# FiveLEDs.net
KiCad netlist of a schematic drawn in EAGLE
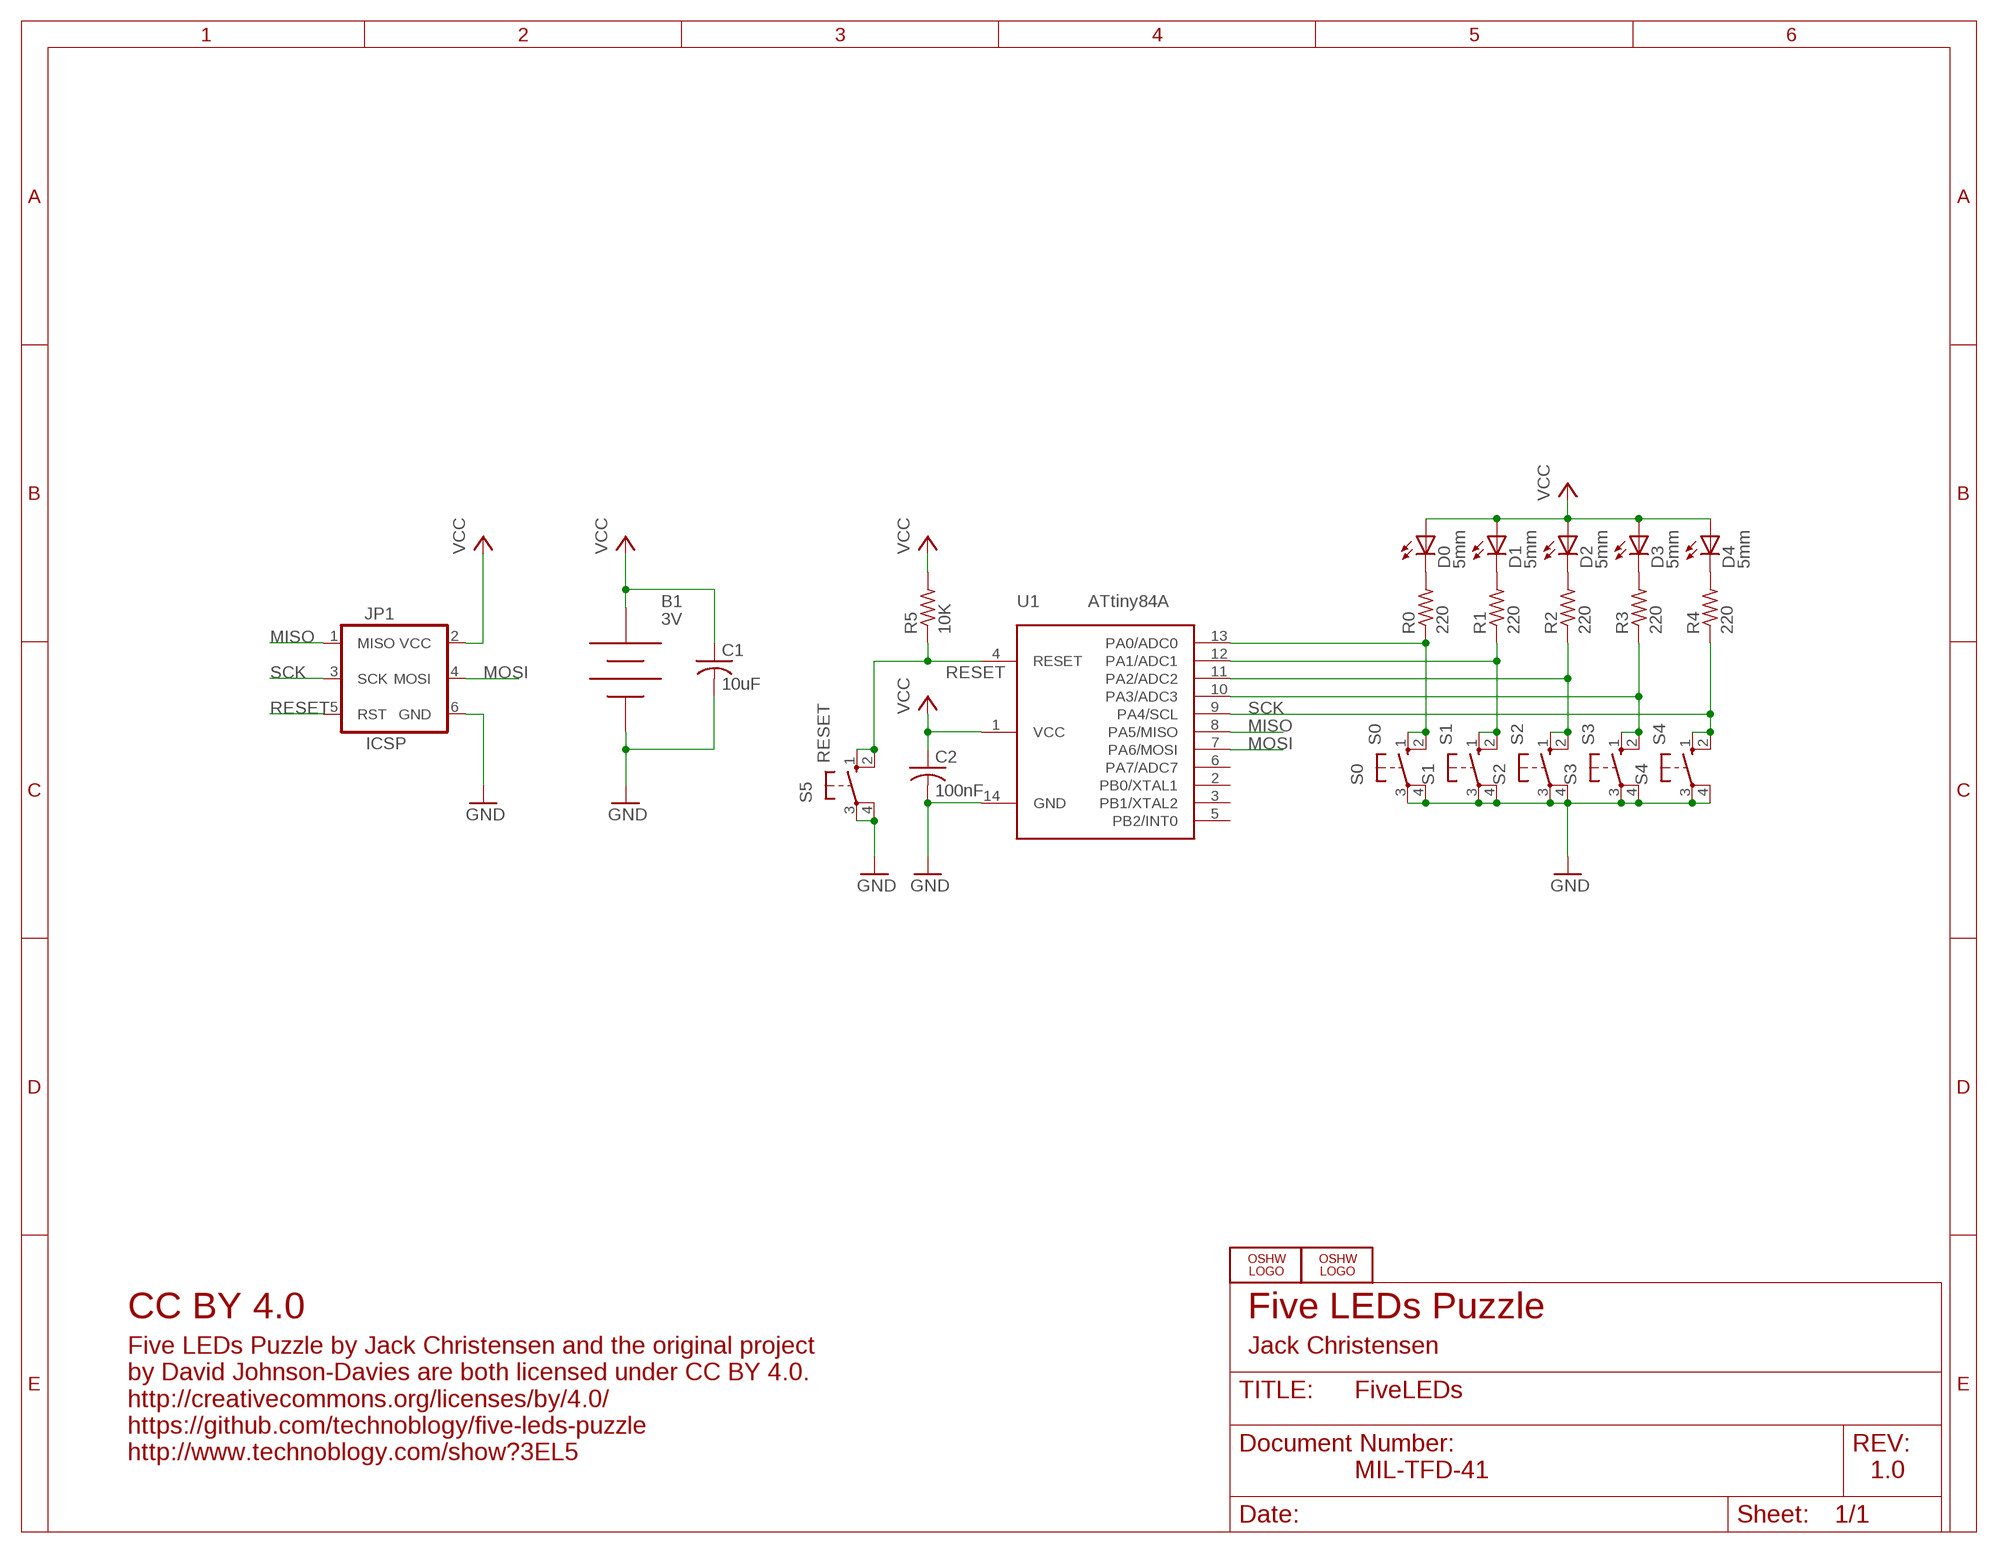
[diagram p0: schematic, sheet 1]

(export (version "E")
  (design (tool "Eeschema 10.0.6"))
  (components
    (comp (ref "B1")
      (value "3V")
      (footprint "eagle-import:KEYSTONE-2462-NO-HOLES")
      (libsource (lib "eagle-import") (part "BATTERY-2AANOHOLES"))
    )
    (comp (ref "C1")
      (value "10uF")
      (footprint "eagle-import:M0805")
      (libsource (lib "eagle-import") (part "C-USM0805"))
    )
    (comp (ref "C2")
      (value "100nF")
      (footprint "eagle-import:M0805")
      (libsource (lib "eagle-import") (part "C-USM0805"))
    )
    (comp (ref "D0")
      (value "5mm")
      (footprint "eagle-import:LED5MM")
      (libsource (lib "eagle-import") (part "LED5MM"))
    )
    (comp (ref "D1")
      (value "5mm")
      (footprint "eagle-import:LED5MM")
      (libsource (lib "eagle-import") (part "LED5MM"))
    )
    (comp (ref "D2")
      (value "5mm")
      (footprint "eagle-import:LED5MM")
      (libsource (lib "eagle-import") (part "LED5MM"))
    )
    (comp (ref "D3")
      (value "5mm")
      (footprint "eagle-import:LED5MM")
      (libsource (lib "eagle-import") (part "LED5MM"))
    )
    (comp (ref "D4")
      (value "5mm")
      (footprint "eagle-import:LED5MM")
      (libsource (lib "eagle-import") (part "LED5MM"))
    )
    (comp (ref "JP1")
      (value "ICSP")
      (footprint "eagle-import:2X3_LOCK")
      (libsource (lib "eagle-import") (part "AVR_SPI_PRG_62X3_LOCK"))
    )
    (comp (ref "LOGO1")
      (value "OSHW_LOGO_8MILX0150-NT")
      (footprint "eagle-import:OSHW_8X150_NOTEXT")
      (libsource (lib "eagle-import") (part "OSHW_LOGO_8MILX0150-NT"))
    )
    (comp (ref "LOGO3")
      (value "OSHW_LOGO_8MILX0100-NT")
      (footprint "eagle-import:OSHW_8X100_NOTEXT")
      (libsource (lib "eagle-import") (part "OSHW_LOGO_8MILX0100-NT"))
    )
    (comp (ref "R0")
      (value "220")
      (footprint "eagle-import:M0805")
      (libsource (lib "eagle-import") (part "R-US_M0805"))
    )
    (comp (ref "R1")
      (value "220")
      (footprint "eagle-import:M0805")
      (libsource (lib "eagle-import") (part "R-US_M0805"))
    )
    (comp (ref "R2")
      (value "220")
      (footprint "eagle-import:M0805")
      (libsource (lib "eagle-import") (part "R-US_M0805"))
    )
    (comp (ref "R3")
      (value "220")
      (footprint "eagle-import:M0805")
      (libsource (lib "eagle-import") (part "R-US_M0805"))
    )
    (comp (ref "R4")
      (value "220")
      (footprint "eagle-import:M0805")
      (libsource (lib "eagle-import") (part "R-US_M0805"))
    )
    (comp (ref "R5")
      (value "10K")
      (footprint "eagle-import:M0805")
      (libsource (lib "eagle-import") (part "R-US_M0805"))
    )
    (comp (ref "S0")
      (value "S0")
      (footprint "eagle-import:B3F-10XXOCT")
      (libsource (lib "eagle-import") (part "10-XXOCT"))
    )
    (comp (ref "S1")
      (value "S1")
      (footprint "eagle-import:B3F-10XXOCT")
      (libsource (lib "eagle-import") (part "10-XXOCT"))
    )
    (comp (ref "S2")
      (value "S2")
      (footprint "eagle-import:B3F-10XXOCT")
      (libsource (lib "eagle-import") (part "10-XXOCT"))
    )
    (comp (ref "S3")
      (value "S3")
      (footprint "eagle-import:B3F-10XXOCT")
      (libsource (lib "eagle-import") (part "10-XXOCT"))
    )
    (comp (ref "S4")
      (value "S4")
      (footprint "eagle-import:B3F-10XXOCT")
      (libsource (lib "eagle-import") (part "10-XXOCT"))
    )
    (comp (ref "S5")
      (value "RESET")
      (footprint "eagle-import:B3F-10XXOCT")
      (libsource (lib "eagle-import") (part "10-XXOCT"))
    )
    (comp (ref "U1")
      (value "ATtiny84A")
      (footprint "eagle-import:SO14")
      (libsource (lib "eagle-import") (part "ATTINYX4SO14"))
    )
  )
  (nets
    (net (code "1") (name "/MISO") (class "Default")
      (node (ref "JP1") (pin "1") (pinfunction "MISO_1") (pintype "passive"))
      (node (ref "U1") (pin "8") (pinfunction "PA5/MISO_8") (pintype "bidirectional"))
    )
    (net (code "2") (name "/MOSI") (class "Default")
      (node (ref "JP1") (pin "4") (pinfunction "MOSI_4") (pintype "passive"))
      (node (ref "U1") (pin "7") (pinfunction "PA6/MOSI_7") (pintype "bidirectional"))
    )
    (net (code "3") (name "/RESET") (class "Default")
      (node (ref "JP1") (pin "5") (pinfunction "RST_5") (pintype "passive"))
      (node (ref "R5") (pin "1") (pinfunction "1_1") (pintype "passive"))
      (node (ref "S5") (pin "1") (pinfunction "S_1") (pintype "passive"))
      (node (ref "S5") (pin "2") (pinfunction "S1_2") (pintype "passive"))
      (node (ref "U1") (pin "4") (pinfunction "RESET_4") (pintype "bidirectional"))
    )
    (net (code "4") (name "/SCK") (class "Default")
      (node (ref "JP1") (pin "3") (pinfunction "SCK_3") (pintype "passive"))
      (node (ref "R4") (pin "1") (pinfunction "1_1") (pintype "passive"))
      (node (ref "S4") (pin "1") (pinfunction "S_1") (pintype "passive"))
      (node (ref "S4") (pin "2") (pinfunction "S1_2") (pintype "passive"))
      (node (ref "U1") (pin "9") (pinfunction "PA4/SCL_9") (pintype "bidirectional"))
    )
    (net (code "5") (name "GND") (class "Default")
      (node (ref "B1") (pin "NEG") (pinfunction "NEG_NEG") (pintype "bidirectional"))
      (node (ref "C1") (pin "2") (pinfunction "2_2") (pintype "passive"))
      (node (ref "C2") (pin "2") (pinfunction "2_2") (pintype "passive"))
      (node (ref "JP1") (pin "6") (pinfunction "GND_6") (pintype "passive"))
      (node (ref "S0") (pin "3") (pinfunction "P_3") (pintype "passive"))
      (node (ref "S0") (pin "4") (pinfunction "P1_4") (pintype "passive"))
      (node (ref "S1") (pin "3") (pinfunction "P_3") (pintype "passive"))
      (node (ref "S1") (pin "4") (pinfunction "P1_4") (pintype "passive"))
      (node (ref "S2") (pin "3") (pinfunction "P_3") (pintype "passive"))
      (node (ref "S2") (pin "4") (pinfunction "P1_4") (pintype "passive"))
      (node (ref "S3") (pin "3") (pinfunction "P_3") (pintype "passive"))
      (node (ref "S3") (pin "4") (pinfunction "P1_4") (pintype "passive"))
      (node (ref "S4") (pin "3") (pinfunction "P_3") (pintype "passive"))
      (node (ref "S4") (pin "4") (pinfunction "P1_4") (pintype "passive"))
      (node (ref "S5") (pin "3") (pinfunction "P_3") (pintype "passive"))
      (node (ref "S5") (pin "4") (pinfunction "P1_4") (pintype "passive"))
      (node (ref "U1") (pin "14") (pinfunction "GND_14") (pintype "bidirectional"))
    )
    (net (code "6") (name "Net-(D0-C)") (class "Default")
      (node (ref "D0") (pin "K") (pinfunction "C_K") (pintype "passive"))
      (node (ref "R0") (pin "2") (pinfunction "2_2") (pintype "passive"))
    )
    (net (code "7") (name "Net-(D1-C)") (class "Default")
      (node (ref "D1") (pin "K") (pinfunction "C_K") (pintype "passive"))
      (node (ref "R1") (pin "2") (pinfunction "2_2") (pintype "passive"))
    )
    (net (code "8") (name "Net-(D2-C)") (class "Default")
      (node (ref "D2") (pin "K") (pinfunction "C_K") (pintype "passive"))
      (node (ref "R2") (pin "2") (pinfunction "2_2") (pintype "passive"))
    )
    (net (code "9") (name "Net-(D3-C)") (class "Default")
      (node (ref "D3") (pin "K") (pinfunction "C_K") (pintype "passive"))
      (node (ref "R3") (pin "2") (pinfunction "2_2") (pintype "passive"))
    )
    (net (code "10") (name "Net-(D4-C)") (class "Default")
      (node (ref "D4") (pin "K") (pinfunction "C_K") (pintype "passive"))
      (node (ref "R4") (pin "2") (pinfunction "2_2") (pintype "passive"))
    )
    (net (code "11") (name "Net-(S0-S)") (class "Default")
      (node (ref "R0") (pin "1") (pinfunction "1_1") (pintype "passive"))
      (node (ref "S0") (pin "1") (pinfunction "S_1") (pintype "passive"))
      (node (ref "S0") (pin "2") (pinfunction "S1_2") (pintype "passive"))
      (node (ref "U1") (pin "13") (pinfunction "PA0/ADC0_13") (pintype "bidirectional"))
    )
    (net (code "12") (name "Net-(S1-S)") (class "Default")
      (node (ref "R1") (pin "1") (pinfunction "1_1") (pintype "passive"))
      (node (ref "S1") (pin "1") (pinfunction "S_1") (pintype "passive"))
      (node (ref "S1") (pin "2") (pinfunction "S1_2") (pintype "passive"))
      (node (ref "U1") (pin "12") (pinfunction "PA1/ADC1_12") (pintype "bidirectional"))
    )
    (net (code "13") (name "Net-(S2-S)") (class "Default")
      (node (ref "R2") (pin "1") (pinfunction "1_1") (pintype "passive"))
      (node (ref "S2") (pin "1") (pinfunction "S_1") (pintype "passive"))
      (node (ref "S2") (pin "2") (pinfunction "S1_2") (pintype "passive"))
      (node (ref "U1") (pin "11") (pinfunction "PA2/ADC2_11") (pintype "bidirectional"))
    )
    (net (code "14") (name "Net-(S3-S)") (class "Default")
      (node (ref "R3") (pin "1") (pinfunction "1_1") (pintype "passive"))
      (node (ref "S3") (pin "1") (pinfunction "S_1") (pintype "passive"))
      (node (ref "S3") (pin "2") (pinfunction "S1_2") (pintype "passive"))
      (node (ref "U1") (pin "10") (pinfunction "PA3/ADC3_10") (pintype "bidirectional"))
    )
    (net (code "15") (name "VCC") (class "Default")
      (node (ref "B1") (pin "POS") (pinfunction "POS_POS") (pintype "bidirectional"))
      (node (ref "C1") (pin "1") (pinfunction "1_1") (pintype "passive"))
      (node (ref "C2") (pin "1") (pinfunction "1_1") (pintype "passive"))
      (node (ref "D0") (pin "A") (pinfunction "A_A") (pintype "passive"))
      (node (ref "D1") (pin "A") (pinfunction "A_A") (pintype "passive"))
      (node (ref "D2") (pin "A") (pinfunction "A_A") (pintype "passive"))
      (node (ref "D3") (pin "A") (pinfunction "A_A") (pintype "passive"))
      (node (ref "D4") (pin "A") (pinfunction "A_A") (pintype "passive"))
      (node (ref "JP1") (pin "2") (pinfunction "VCC_2") (pintype "passive"))
      (node (ref "R5") (pin "2") (pinfunction "2_2") (pintype "passive"))
      (node (ref "U1") (pin "1") (pinfunction "VCC_1") (pintype "bidirectional"))
    )
    (net (code "16") (name "unconnected-(U1-PA7{slash}ADC7-Pad6)") (class "Default")
      (node (ref "U1") (pin "6") (pinfunction "PA7/ADC7_6") (pintype "bidirectional"))
    )
    (net (code "17") (name "unconnected-(U1-PB0{slash}XTAL1-Pad2)") (class "Default")
      (node (ref "U1") (pin "2") (pinfunction "PB0/XTAL1_2") (pintype "bidirectional"))
    )
    (net (code "18") (name "unconnected-(U1-PB1{slash}XTAL2-Pad3)") (class "Default")
      (node (ref "U1") (pin "3") (pinfunction "PB1/XTAL2_3") (pintype "bidirectional"))
    )
    (net (code "19") (name "unconnected-(U1-PB2{slash}INT0-Pad5)") (class "Default")
      (node (ref "U1") (pin "5") (pinfunction "PB2/INT0_5") (pintype "bidirectional"))
    )
  )
)
